# Power.net
KiCad netlist of a schematic drawn in Altium Designer
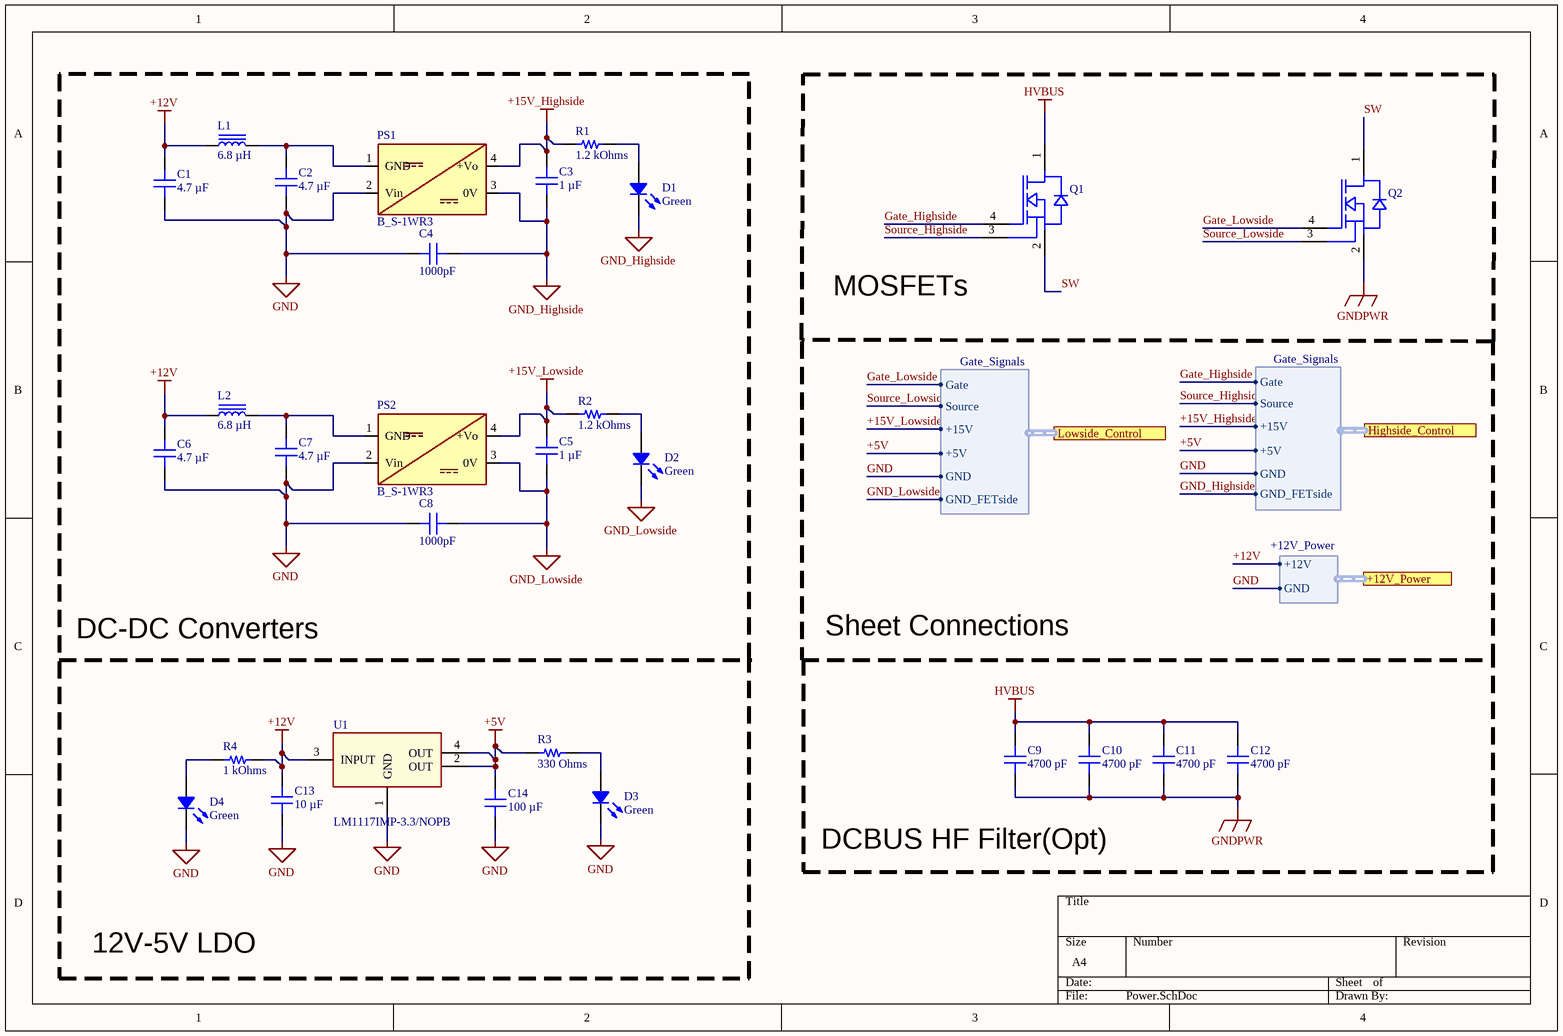
[diagram p0: Power.SchDoc]

(export (version "E")
  (design (tool "Eeschema 10.0.6"))
  (components
    (comp (ref "C1")
      (value "4.7 µF")
      (footprint "CAP 0805_2012")
      (description "CAP CER 4.7UF 10V Y5V 0805")
      (fields
        (field (name "PART NUMBER") "VJ0805V475ZXQTW1BC")
        (field (name "MANUFACTURER") "Vishay Vitramon")
      )
      (libsource (lib "Celestial Altium Library - altium_library (2)") (part "Capacitor"))
    )
    (comp (ref "C2")
      (value "4.7 µF")
      (footprint "CAP 0805_2012")
      (description "CAP CER 4.7UF 10V Y5V 0805")
      (fields
        (field (name "PART NUMBER") "VJ0805V475ZXQTW1BC")
        (field (name "MANUFACTURER") "Vishay Vitramon")
      )
      (libsource (lib "Celestial Altium Library - altium_library (2)") (part "Capacitor"))
    )
    (comp (ref "C3")
      (value "1 µF")
      (footprint "CAP 0805_2012")
      (description "CAP CER 1UF 25V X7R 0805")
      (fields
        (field (name "PART NUMBER") "VJ0805Y105KXXTW1BC")
        (field (name "MANUFACTURER") "Vishay Vitramon")
      )
      (libsource (lib "Celestial Altium Library - altium_library (2)") (part "Capacitor"))
    )
    (comp (ref "C4")
      (value "1000pF")
      (footprint "CAP 1210_3225 - 1.8MM")
      (description "CAP CER 1000PF 2KV X7R 1210")
      (fields (field (name "PART NUMBER") "1210GC102MAT1A") (field (name "MANUFACTURER") "AVX Corporation"))
      (libsource (lib "Celestial Altium Library - altium_library (2)") (part "Capacitor"))
    )
    (comp (ref "C5")
      (value "1 µF")
      (footprint "CAP 0805_2012")
      (description "CAP CER 1UF 25V X7R 0805")
      (fields
        (field (name "PART NUMBER") "VJ0805Y105KXXTW1BC")
        (field (name "MANUFACTURER") "Vishay Vitramon")
      )
      (libsource (lib "Celestial Altium Library - altium_library (2)") (part "Capacitor"))
    )
    (comp (ref "C6")
      (value "4.7 µF")
      (footprint "CAP 0805_2012")
      (description "CAP CER 4.7UF 10V Y5V 0805")
      (fields
        (field (name "PART NUMBER") "VJ0805V475ZXQTW1BC")
        (field (name "MANUFACTURER") "Vishay Vitramon")
      )
      (libsource (lib "Celestial Altium Library - altium_library (2)") (part "Capacitor"))
    )
    (comp (ref "C7")
      (value "4.7 µF")
      (footprint "CAP 0805_2012")
      (description "CAP CER 4.7UF 10V Y5V 0805")
      (fields
        (field (name "PART NUMBER") "VJ0805V475ZXQTW1BC")
        (field (name "MANUFACTURER") "Vishay Vitramon")
      )
      (libsource (lib "Celestial Altium Library - altium_library (2)") (part "Capacitor"))
    )
    (comp (ref "C8")
      (value "1000pF")
      (footprint "CAP 1210_3225 - 1.8MM")
      (description "CAP CER 1000PF 2KV X7R 1210")
      (fields (field (name "PART NUMBER") "1210GC102MAT1A") (field (name "MANUFACTURER") "AVX Corporation"))
      (libsource (lib "Celestial Altium Library - altium_library (2)") (part "Capacitor"))
    )
    (comp (ref "C9")
      (value "4700 pF")
      (footprint "CAP 1206_3216 - 0.8MM")
      (description "CAP CER 4700PF 1KV X7R 1206")
      (fields (field (name "PART NUMBER") "C1206X472KDRACAUTO") (field (name "MANUFACTURER") "KEMET"))
      (libsource (lib "Celestial Altium Library - altium_library (2)") (part "Capacitor"))
    )
    (comp (ref "C10")
      (value "4700 pF")
      (footprint "CAP 1206_3216 - 0.8MM")
      (description "CAP CER 4700PF 1KV X7R 1206")
      (fields (field (name "PART NUMBER") "C1206X472KDRACAUTO") (field (name "MANUFACTURER") "KEMET"))
      (libsource (lib "Celestial Altium Library - altium_library (2)") (part "Capacitor"))
    )
    (comp (ref "C11")
      (value "4700 pF")
      (footprint "CAP 1206_3216 - 0.8MM")
      (description "CAP CER 4700PF 1KV X7R 1206")
      (fields (field (name "PART NUMBER") "C1206X472KDRACAUTO") (field (name "MANUFACTURER") "KEMET"))
      (libsource (lib "Celestial Altium Library - altium_library (2)") (part "Capacitor"))
    )
    (comp (ref "C12")
      (value "4700 pF")
      (footprint "CAP 1206_3216 - 0.8MM")
      (description "CAP CER 4700PF 1KV X7R 1206")
      (fields (field (name "PART NUMBER") "C1206X472KDRACAUTO") (field (name "MANUFACTURER") "KEMET"))
      (libsource (lib "Celestial Altium Library - altium_library (2)") (part "Capacitor"))
    )
    (comp (ref "C13")
      (value "10 µF")
      (footprint "CAP 0805_2012")
      (description "CAP CER 10UF 25V X6S 0805")
      (fields (field (name "PART NUMBER") "TMK212BC6106MG-T") (field (name "MANUFACTURER") "Taiyo Yuden"))
      (libsource (lib "Celestial Altium Library - altium_library (2)") (part "Capacitor"))
    )
    (comp (ref "C14")
      (value "100 µF")
      (footprint "CAP 0805_2012")
      (description "CAP CER 100UF 6.3V X5R 0805")
      (fields (field (name "PART NUMBER") "MSASJ21GBB5107MTCA01") (field (name "MANUFACTURER") "Taiyo Yuden"))
      (libsource (lib "Celestial Altium Library - altium_library (2)") (part "Capacitor"))
    )
    (comp (ref "D1")
      (value "Green")
      (footprint "LED 0805_2012 GREEN")
      (description "LED GREEN DIFFUSED CHIP SMD")
      (fields (field (name "PART NUMBER") "HSMQ-C170") (field (name "MANUFACTURER") "Broadcom Limited"))
      (libsource (lib "Celestial Altium Library - altium_library (2)") (part "LED"))
    )
    (comp (ref "D2")
      (value "Green")
      (footprint "LED 0805_2012 GREEN")
      (description "LED GREEN DIFFUSED CHIP SMD")
      (fields (field (name "PART NUMBER") "HSMQ-C170") (field (name "MANUFACTURER") "Broadcom Limited"))
      (libsource (lib "Celestial Altium Library - altium_library (2)") (part "LED"))
    )
    (comp (ref "D3")
      (value "Green")
      (footprint "LED 0805_2012 GREEN")
      (description "LED GREEN DIFFUSED CHIP SMD")
      (fields (field (name "PART NUMBER") "HSMQ-C170") (field (name "MANUFACTURER") "Broadcom Limited"))
      (libsource (lib "Celestial Altium Library - altium_library (2)") (part "LED"))
    )
    (comp (ref "D4")
      (value "Green")
      (footprint "LED 0805_2012 GREEN")
      (description "LED GREEN DIFFUSED CHIP SMD")
      (fields (field (name "PART NUMBER") "HSMQ-C170") (field (name "MANUFACTURER") "Broadcom Limited"))
      (libsource (lib "Celestial Altium Library - altium_library (2)") (part "LED"))
    )
    (comp (ref "L1")
      (value "6.8 µH")
      (footprint "TDK VLCF4024-2")
      (description "FIXED IND 6.8UH 1.15A 116MOHM SM")
      (fields
        (field (name "PART NUMBER") "VLCF4024T-6R8N1R1-2")
        (field (name "MANUFACTURER") "TDK Corporation")
      )
      (libsource (lib "Celestial Altium Library - altium_library (2)") (part "Inductor"))
    )
    (comp (ref "L2")
      (value "6.8 µH")
      (footprint "TDK VLCF4024-2")
      (description "FIXED IND 6.8UH 1.15A 116MOHM SM")
      (fields
        (field (name "PART NUMBER") "VLCF4024T-6R8N1R1-2")
        (field (name "MANUFACTURER") "TDK Corporation")
      )
      (libsource (lib "Celestial Altium Library - altium_library (2)") (part "Inductor"))
    )
    (comp (ref "PS1") (value "B_S-1WR3") (footprint "B_S-1WR3") (libsource (lib "Schlib1") (part "B_S-1WR3")))
    (comp (ref "PS2") (value "B_S-1WR3") (footprint "B_S-1WR3") (libsource (lib "Schlib1") (part "B_S-1WR3")))
    (comp (ref "Q1")
      (value "NTH4L015N065SC1")
      (footprint "NTH4L015N065SC1")
      (fields (field (name "MOUSER PART NUMBER") "863-NTH4L015N065SC1"))
      (libsource (lib "Schlib1") (part "NTH4L015N065SC1"))
    )
    (comp (ref "Q2")
      (value "NTH4L015N065SC1")
      (footprint "NTH4L015N065SC1")
      (fields (field (name "MOUSER PART NUMBER") "863-NTH4L015N065SC1"))
      (libsource (lib "Schlib1") (part "NTH4L015N065SC1"))
    )
    (comp (ref "R1")
      (value "1.2 kOhms")
      (footprint "RES 0805_2012")
      (description "RES SMD 1.2K OHM 0.1% 1/10W 0805")
      (fields
        (field (name "PART NUMBER") "CPF0805B1K2E1")
        (field (name "MANUFACTURER") "TE Connectivity Passive Product")
      )
      (libsource (lib "Celestial Altium Library - altium_library (2)") (part "Resistor"))
    )
    (comp (ref "R2")
      (value "1.2 kOhms")
      (footprint "RES 0805_2012")
      (description "RES SMD 1.2K OHM 0.1% 1/10W 0805")
      (fields
        (field (name "PART NUMBER") "CPF0805B1K2E1")
        (field (name "MANUFACTURER") "TE Connectivity Passive Product")
      )
      (libsource (lib "Celestial Altium Library - altium_library (2)") (part "Resistor"))
    )
    (comp (ref "R3")
      (value "330 Ohms")
      (footprint "RES 0805_2012")
      (description "RES SMD 330 OHM 0.1% 1/10W 0805")
      (fields
        (field (name "PART NUMBER") "CPF0805B330RE1")
        (field (name "MANUFACTURER") "TE Connectivity Passive Product")
      )
      (libsource (lib "Celestial Altium Library - altium_library (2)") (part "Resistor"))
    )
    (comp (ref "R4")
      (value "1 kOhms")
      (footprint "RES 0805_2012")
      (description "RES SMD 1K OHM 0.1% 1/4W 0805")
      (fields
        (field (name "PART NUMBER") "1-2176092-8")
        (field (name "MANUFACTURER") "TE Connectivity Passive Product")
      )
      (libsource (lib "Celestial Altium Library - altium_library (2)") (part "Resistor"))
    )
    (comp (ref "U1")
      (value "LM1117IMP-3.3/NOPB")
      (footprint "DCY0004A_M")
      (description "800-mA 15-V linear voltage regulator 4-SOT-223 -40 to 125")
      (fields (field (name "COPYRIGHT") "Copyright (C) 2025 Ultra Librarian. All rights reserved."))
      (libsource (lib "Schlib1") (part "LM1117IMP-3.3NOPB"))
    )
  )
  (nets
    (net (code "3") (name "+5V") (class "Default")
      (node (ref "C14") (pin "2") (pinfunction "2_2") (pintype "passive"))
      (node (ref "R3") (pin "1") (pinfunction "1_1") (pintype "passive"))
      (node (ref "U1") (pin "2") (pinfunction "OUT_2") (pintype "power_in"))
      (node (ref "U1") (pin "4") (pinfunction "OUT_4") (pintype "power_in"))
    )
    (net (code "4") (name "+12V") (class "Default")
      (node (ref "C1") (pin "2") (pinfunction "2_2") (pintype "passive"))
      (node (ref "C13") (pin "2") (pinfunction "2_2") (pintype "passive"))
      (node (ref "C6") (pin "2") (pinfunction "2_2") (pintype "passive"))
      (node (ref "L1") (pin "1") (pinfunction "1_1") (pintype "passive"))
      (node (ref "L2") (pin "1") (pinfunction "1_1") (pintype "passive"))
      (node (ref "R4") (pin "2") (pinfunction "2_2") (pintype "passive"))
      (node (ref "U1") (pin "3") (pinfunction "INPUT_3") (pintype "power_in"))
    )
    (net (code "5") (name "+15V_Highside") (class "Default")
      (node (ref "C3") (pin "2") (pinfunction "2_2") (pintype "passive"))
      (node (ref "PS1") (pin "4") (pinfunction "+Vo_4") (pintype "passive"))
      (node (ref "R1") (pin "1") (pinfunction "1_1") (pintype "passive"))
    )
    (net (code "6") (name "+15V_Lowside") (class "Default")
      (node (ref "C5") (pin "2") (pinfunction "2_2") (pintype "passive"))
      (node (ref "PS2") (pin "4") (pinfunction "+Vo_4") (pintype "passive"))
      (node (ref "R2") (pin "1") (pinfunction "1_1") (pintype "passive"))
    )
    (net (code "7") (name "/Gate_Highside") (class "Default")
      (node (ref "Q1") (pin "4") (pinfunction "G_4") (pintype "passive"))
    )
    (net (code "8") (name "/Gate_Lowside") (class "Default")
      (node (ref "Q2") (pin "4") (pinfunction "G_4") (pintype "passive"))
    )
    (net (code "9") (name "/SW") (class "Default")
      (node (ref "Q1") (pin "2") (pinfunction "S2_2") (pintype "passive"))
      (node (ref "Q2") (pin "1") (pinfunction "D_1") (pintype "passive"))
    )
    (net (code "10") (name "/Source_Highside") (class "Default")
      (node (ref "Q1") (pin "3") (pinfunction "S1_3") (pintype "passive"))
    )
    (net (code "11") (name "/Source_Lowside") (class "Default")
      (node (ref "Q2") (pin "3") (pinfunction "S1_3") (pintype "passive"))
    )
    (net (code "14") (name "GND") (class "Default")
      (node (ref "C1") (pin "1") (pinfunction "1_1") (pintype "passive"))
      (node (ref "C13") (pin "1") (pinfunction "1_1") (pintype "passive"))
      (node (ref "C14") (pin "1") (pinfunction "1_1") (pintype "passive"))
      (node (ref "C2") (pin "1") (pinfunction "1_1") (pintype "passive"))
      (node (ref "C4") (pin "1") (pinfunction "1_1") (pintype "passive"))
      (node (ref "C6") (pin "1") (pinfunction "1_1") (pintype "passive"))
      (node (ref "C7") (pin "1") (pinfunction "1_1") (pintype "passive"))
      (node (ref "C8") (pin "1") (pinfunction "1_1") (pintype "passive"))
      (node (ref "D3") (pin "2") (pinfunction "2_2") (pintype "passive"))
      (node (ref "D4") (pin "2") (pinfunction "2_2") (pintype "passive"))
      (node (ref "PS1") (pin "2") (pinfunction "Vin_2") (pintype "passive"))
      (node (ref "PS2") (pin "2") (pinfunction "Vin_2") (pintype "passive"))
      (node (ref "U1") (pin "1") (pinfunction "GND_1") (pintype "power_in"))
    )
    (net (code "15") (name "GNDPWR") (class "Default")
      (node (ref "C10") (pin "1") (pinfunction "1_1") (pintype "passive"))
      (node (ref "C11") (pin "1") (pinfunction "1_1") (pintype "passive"))
      (node (ref "C12") (pin "1") (pinfunction "1_1") (pintype "passive"))
      (node (ref "C9") (pin "1") (pinfunction "1_1") (pintype "passive"))
      (node (ref "Q2") (pin "2") (pinfunction "S2_2") (pintype "passive"))
    )
    (net (code "16") (name "GND_Highside") (class "Default")
      (node (ref "C3") (pin "1") (pinfunction "1_1") (pintype "passive"))
      (node (ref "C4") (pin "2") (pinfunction "2_2") (pintype "passive"))
      (node (ref "D1") (pin "2") (pinfunction "2_2") (pintype "passive"))
      (node (ref "PS1") (pin "3") (pinfunction "0V_3") (pintype "passive"))
    )
    (net (code "17") (name "GND_Lowside") (class "Default")
      (node (ref "C5") (pin "1") (pinfunction "1_1") (pintype "passive"))
      (node (ref "C8") (pin "2") (pinfunction "2_2") (pintype "passive"))
      (node (ref "D2") (pin "2") (pinfunction "2_2") (pintype "passive"))
      (node (ref "PS2") (pin "3") (pinfunction "0V_3") (pintype "passive"))
    )
    (net (code "18") (name "HVBUS") (class "Default")
      (node (ref "C10") (pin "2") (pinfunction "2_2") (pintype "passive"))
      (node (ref "C11") (pin "2") (pinfunction "2_2") (pintype "passive"))
      (node (ref "C12") (pin "2") (pinfunction "2_2") (pintype "passive"))
      (node (ref "C9") (pin "2") (pinfunction "2_2") (pintype "passive"))
      (node (ref "Q1") (pin "1") (pinfunction "D_1") (pintype "passive"))
    )
    (net (code "19") (name "Net-(D1-Pad1)") (class "Default")
      (node (ref "D1") (pin "1") (pinfunction "1_1") (pintype "passive"))
      (node (ref "R1") (pin "2") (pinfunction "2_2") (pintype "passive"))
    )
    (net (code "20") (name "Net-(D2-Pad1)") (class "Default")
      (node (ref "D2") (pin "1") (pinfunction "1_1") (pintype "passive"))
      (node (ref "R2") (pin "2") (pinfunction "2_2") (pintype "passive"))
    )
    (net (code "21") (name "Net-(D3-Pad1)") (class "Default")
      (node (ref "D3") (pin "1") (pinfunction "1_1") (pintype "passive"))
      (node (ref "R3") (pin "2") (pinfunction "2_2") (pintype "passive"))
    )
    (net (code "22") (name "Net-(D4-Pad1)") (class "Default")
      (node (ref "D4") (pin "1") (pinfunction "1_1") (pintype "passive"))
      (node (ref "R4") (pin "1") (pinfunction "1_1") (pintype "passive"))
    )
    (net (code "23") (name "Net-(PS1-GND)") (class "Default")
      (node (ref "C2") (pin "2") (pinfunction "2_2") (pintype "passive"))
      (node (ref "L1") (pin "2") (pinfunction "2_2") (pintype "passive"))
      (node (ref "PS1") (pin "1") (pinfunction "GND_1") (pintype "passive"))
    )
    (net (code "24") (name "Net-(PS2-GND)") (class "Default")
      (node (ref "C7") (pin "2") (pinfunction "2_2") (pintype "passive"))
      (node (ref "L2") (pin "2") (pinfunction "2_2") (pintype "passive"))
      (node (ref "PS2") (pin "1") (pinfunction "GND_1") (pintype "passive"))
    )
  )
)
